# Pi_Power.net
KiCad netlist of a schematic drawn in Altium Designer
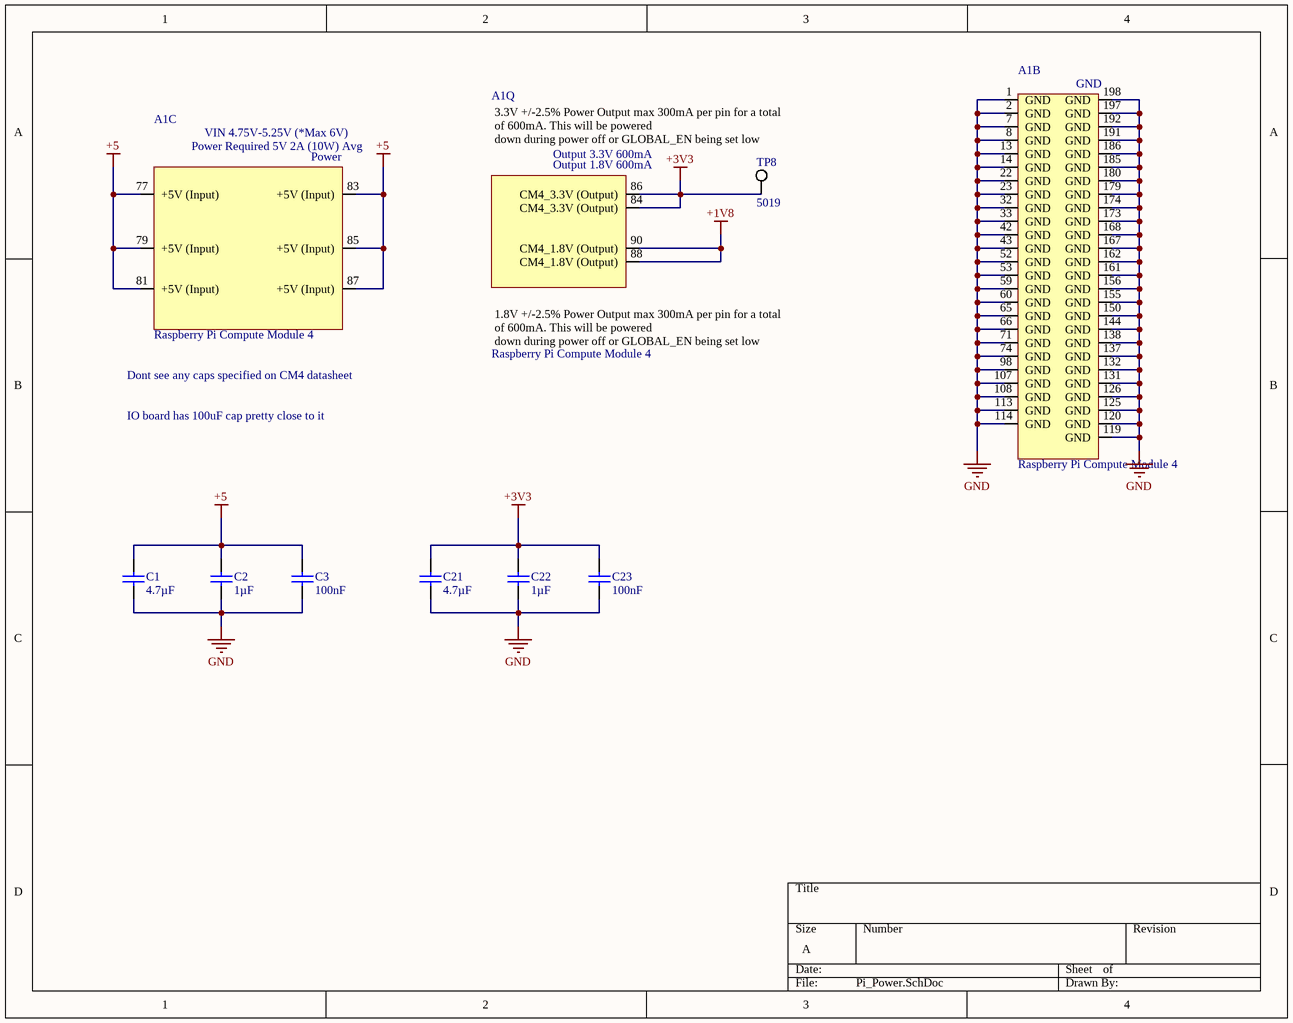
[diagram p0: Pi_Power.SchDoc]

(export (version "E")
  (design (tool "Eeschema 10.0.6"))
  (components
    (comp (ref "A1")
      (value "Raspberry Pi Compute Module 4")
      (footprint "CM4-F40C-100DS-0.4v_1.5mm_0mm")
      (description "Raspberry Pi Compute Module 4 by Amornthep Phunsin")
      (libsource (lib "CM4") (part "CM4"))
    )
    (comp (ref "C1")
      (value "4.7µF")
      (footprint "CAPC0603(1608)100_L")
      (description "Chip Capacitor, 4.7µF +/-20%, 10V, 0603, Thickness 1 mm")
      (fields (field (name "TOLERANCE") "10%") (field (name "MPN") "GRM188Z71A475ME15D"))
      (libsource (lib "Hytech Racing") (part "CAP-NP-2"))
    )
    (comp (ref "C2")
      (value "1µF")
      (footprint "CAPC1608X94X35NL15T15")
      (description "Chip Capacitor, 1 uF, +/- 10%, 16 V, 0603 (1608 Metric)")
      (fields (field (name "TOLERANCE") "10%") (field (name "MPN") "CL10A105KO8NNNC"))
      (libsource (lib "Hytech Racing") (part "CAP-NP-2"))
    )
    (comp (ref "C3")
      (value "100nF")
      (footprint "CAPC1005X56X25LL10T15")
      (description "Chip Capacitor, 0.1 uF, +/- 5%, 16 V, 0402 (1005 Metric)")
      (fields (field (name "TOLERANCE") "5%") (field (name "MFR") "Samsung Electro-Mechanics"))
      (libsource (lib "Hytech Racing") (part "CAP-NP-2"))
    )
    (comp (ref "C21")
      (value "4.7µF")
      (footprint "CAPC0603(1608)100_L")
      (description "Chip Capacitor, 4.7µF +/-20%, 10V, 0603, Thickness 1 mm")
      (fields (field (name "TOLERANCE") "10%") (field (name "MPN") "GRM188Z71A475ME15D"))
      (libsource (lib "Hytech Racing") (part "CAP-NP-2"))
    )
    (comp (ref "C22")
      (value "1µF")
      (footprint "CAPC1608X94X35NL15T15")
      (description "Chip Capacitor, 1 uF, +/- 10%, 16 V, 0603 (1608 Metric)")
      (fields (field (name "TOLERANCE") "10%") (field (name "MPN") "CL10A105KO8NNNC"))
      (libsource (lib "Hytech Racing") (part "CAP-NP-2"))
    )
    (comp (ref "C23")
      (value "100nF")
      (footprint "CAPC1005X56X25LL10T15")
      (description "Chip Capacitor, 0.1 uF, +/- 5%, 16 V, 0402 (1005 Metric)")
      (fields (field (name "TOLERANCE") "5%") (field (name "MFR") "Samsung Electro-Mechanics"))
      (libsource (lib "Hytech Racing") (part "CAP-NP-2"))
    )
    (comp (ref "TP8")
      (value "5019")
      (footprint "KSTN-5019_V")
      (description "Test Point, 1 Position SMD, RoHS, Tape and Reel")
      (fields (field (name "MFR") "Keystone Electronics"))
      (libsource (lib "CM4") (part "CMP-1672-00008-1"))
    )
  )
  (nets
    (net (code "1") (name "+1V8") (class "Default")
      (node (ref "A1") (pin "88") (pinfunction "CM4_1.8V_(Output)_88") (pintype "power_in"))
      (node (ref "A1") (pin "90") (pinfunction "CM4_1.8V_(Output)_90") (pintype "power_in"))
    )
    (net (code "2") (name "+3V3") (class "Default")
      (node (ref "A1") (pin "84") (pinfunction "CM4_3.3V_(Output)_84") (pintype "power_in"))
      (node (ref "A1") (pin "86") (pinfunction "CM4_3.3V_(Output)_86") (pintype "power_in"))
      (node (ref "C21") (pin "2") (pinfunction "2_2") (pintype "passive"))
      (node (ref "C22") (pin "2") (pinfunction "2_2") (pintype "passive"))
      (node (ref "C23") (pin "2") (pinfunction "2_2") (pintype "passive"))
      (node (ref "TP8") (pin "1") (pinfunction "1_1") (pintype "passive"))
    )
    (net (code "3") (name "+5") (class "Default")
      (node (ref "A1") (pin "77") (pinfunction "+5V_(Input)_77") (pintype "power_in"))
      (node (ref "A1") (pin "79") (pinfunction "+5V_(Input)_79") (pintype "power_in"))
      (node (ref "A1") (pin "81") (pinfunction "+5V_(Input)_81") (pintype "power_in"))
      (node (ref "A1") (pin "83") (pinfunction "+5V_(Input)_83") (pintype "power_in"))
      (node (ref "A1") (pin "85") (pinfunction "+5V_(Input)_85") (pintype "power_in"))
      (node (ref "A1") (pin "87") (pinfunction "+5V_(Input)_87") (pintype "power_in"))
      (node (ref "C1") (pin "2") (pinfunction "2_2") (pintype "passive"))
      (node (ref "C2") (pin "2") (pinfunction "2_2") (pintype "passive"))
      (node (ref "C3") (pin "2") (pinfunction "2_2") (pintype "passive"))
    )
    (net (code "4") (name "GND") (class "Default")
      (node (ref "A1") (pin "1") (pinfunction "GND_1") (pintype "power_in"))
      (node (ref "A1") (pin "107") (pinfunction "GND_107") (pintype "power_in"))
      (node (ref "A1") (pin "108") (pinfunction "GND_108") (pintype "power_in"))
      (node (ref "A1") (pin "113") (pinfunction "GND_113") (pintype "power_in"))
      (node (ref "A1") (pin "114") (pinfunction "GND_114") (pintype "power_in"))
      (node (ref "A1") (pin "119") (pinfunction "GND_119") (pintype "power_in"))
      (node (ref "A1") (pin "120") (pinfunction "GND_120") (pintype "power_in"))
      (node (ref "A1") (pin "125") (pinfunction "GND_125") (pintype "power_in"))
      (node (ref "A1") (pin "126") (pinfunction "GND_126") (pintype "power_in"))
      (node (ref "A1") (pin "13") (pinfunction "GND_13") (pintype "power_in"))
      (node (ref "A1") (pin "131") (pinfunction "GND_131") (pintype "power_in"))
      (node (ref "A1") (pin "132") (pinfunction "GND_132") (pintype "power_in"))
      (node (ref "A1") (pin "137") (pinfunction "GND_137") (pintype "power_in"))
      (node (ref "A1") (pin "138") (pinfunction "GND_138") (pintype "power_in"))
      (node (ref "A1") (pin "14") (pinfunction "GND_14") (pintype "power_in"))
      (node (ref "A1") (pin "144") (pinfunction "GND_144") (pintype "power_in"))
      (node (ref "A1") (pin "150") (pinfunction "GND_150") (pintype "power_in"))
      (node (ref "A1") (pin "155") (pinfunction "GND_155") (pintype "power_in"))
      (node (ref "A1") (pin "156") (pinfunction "GND_156") (pintype "power_in"))
      (node (ref "A1") (pin "161") (pinfunction "GND_161") (pintype "power_in"))
      (node (ref "A1") (pin "162") (pinfunction "GND_162") (pintype "power_in"))
      (node (ref "A1") (pin "167") (pinfunction "GND_167") (pintype "power_in"))
      (node (ref "A1") (pin "168") (pinfunction "GND_168") (pintype "power_in"))
      (node (ref "A1") (pin "173") (pinfunction "GND_173") (pintype "power_in"))
      (node (ref "A1") (pin "174") (pinfunction "GND_174") (pintype "power_in"))
      (node (ref "A1") (pin "179") (pinfunction "GND_179") (pintype "power_in"))
      (node (ref "A1") (pin "180") (pinfunction "GND_180") (pintype "power_in"))
      (node (ref "A1") (pin "185") (pinfunction "GND_185") (pintype "power_in"))
      (node (ref "A1") (pin "186") (pinfunction "GND_186") (pintype "power_in"))
      (node (ref "A1") (pin "191") (pinfunction "GND_191") (pintype "power_in"))
      (node (ref "A1") (pin "192") (pinfunction "GND_192") (pintype "power_in"))
      (node (ref "A1") (pin "197") (pinfunction "GND_197") (pintype "power_in"))
      (node (ref "A1") (pin "198") (pinfunction "GND_198") (pintype "power_in"))
      (node (ref "A1") (pin "2") (pinfunction "GND_2") (pintype "power_in"))
      (node (ref "A1") (pin "22") (pinfunction "GND_22") (pintype "power_in"))
      (node (ref "A1") (pin "23") (pinfunction "GND_23") (pintype "power_in"))
      (node (ref "A1") (pin "32") (pinfunction "GND_32") (pintype "power_in"))
      (node (ref "A1") (pin "33") (pinfunction "GND_33") (pintype "power_in"))
      (node (ref "A1") (pin "42") (pinfunction "GND_42") (pintype "power_in"))
      (node (ref "A1") (pin "43") (pinfunction "GND_43") (pintype "power_in"))
      (node (ref "A1") (pin "52") (pinfunction "GND_52") (pintype "power_in"))
      (node (ref "A1") (pin "53") (pinfunction "GND_53") (pintype "power_in"))
      (node (ref "A1") (pin "59") (pinfunction "GND_59") (pintype "power_in"))
      (node (ref "A1") (pin "60") (pinfunction "GND_60") (pintype "power_in"))
      (node (ref "A1") (pin "65") (pinfunction "GND_65") (pintype "power_in"))
      (node (ref "A1") (pin "66") (pinfunction "GND_66") (pintype "power_in"))
      (node (ref "A1") (pin "7") (pinfunction "GND_7") (pintype "power_in"))
      (node (ref "A1") (pin "71") (pinfunction "GND_71") (pintype "power_in"))
      (node (ref "A1") (pin "74") (pinfunction "GND_74") (pintype "power_in"))
      (node (ref "A1") (pin "8") (pinfunction "GND_8") (pintype "power_in"))
      (node (ref "A1") (pin "98") (pinfunction "GND_98") (pintype "power_in"))
      (node (ref "C1") (pin "1") (pinfunction "1_1") (pintype "passive"))
      (node (ref "C2") (pin "1") (pinfunction "1_1") (pintype "passive"))
      (node (ref "C21") (pin "1") (pinfunction "1_1") (pintype "passive"))
      (node (ref "C22") (pin "1") (pinfunction "1_1") (pintype "passive"))
      (node (ref "C23") (pin "1") (pinfunction "1_1") (pintype "passive"))
      (node (ref "C3") (pin "1") (pinfunction "1_1") (pintype "passive"))
    )
  )
)
